# HBridge328.net
KiCad netlist of a schematic drawn in EAGLE
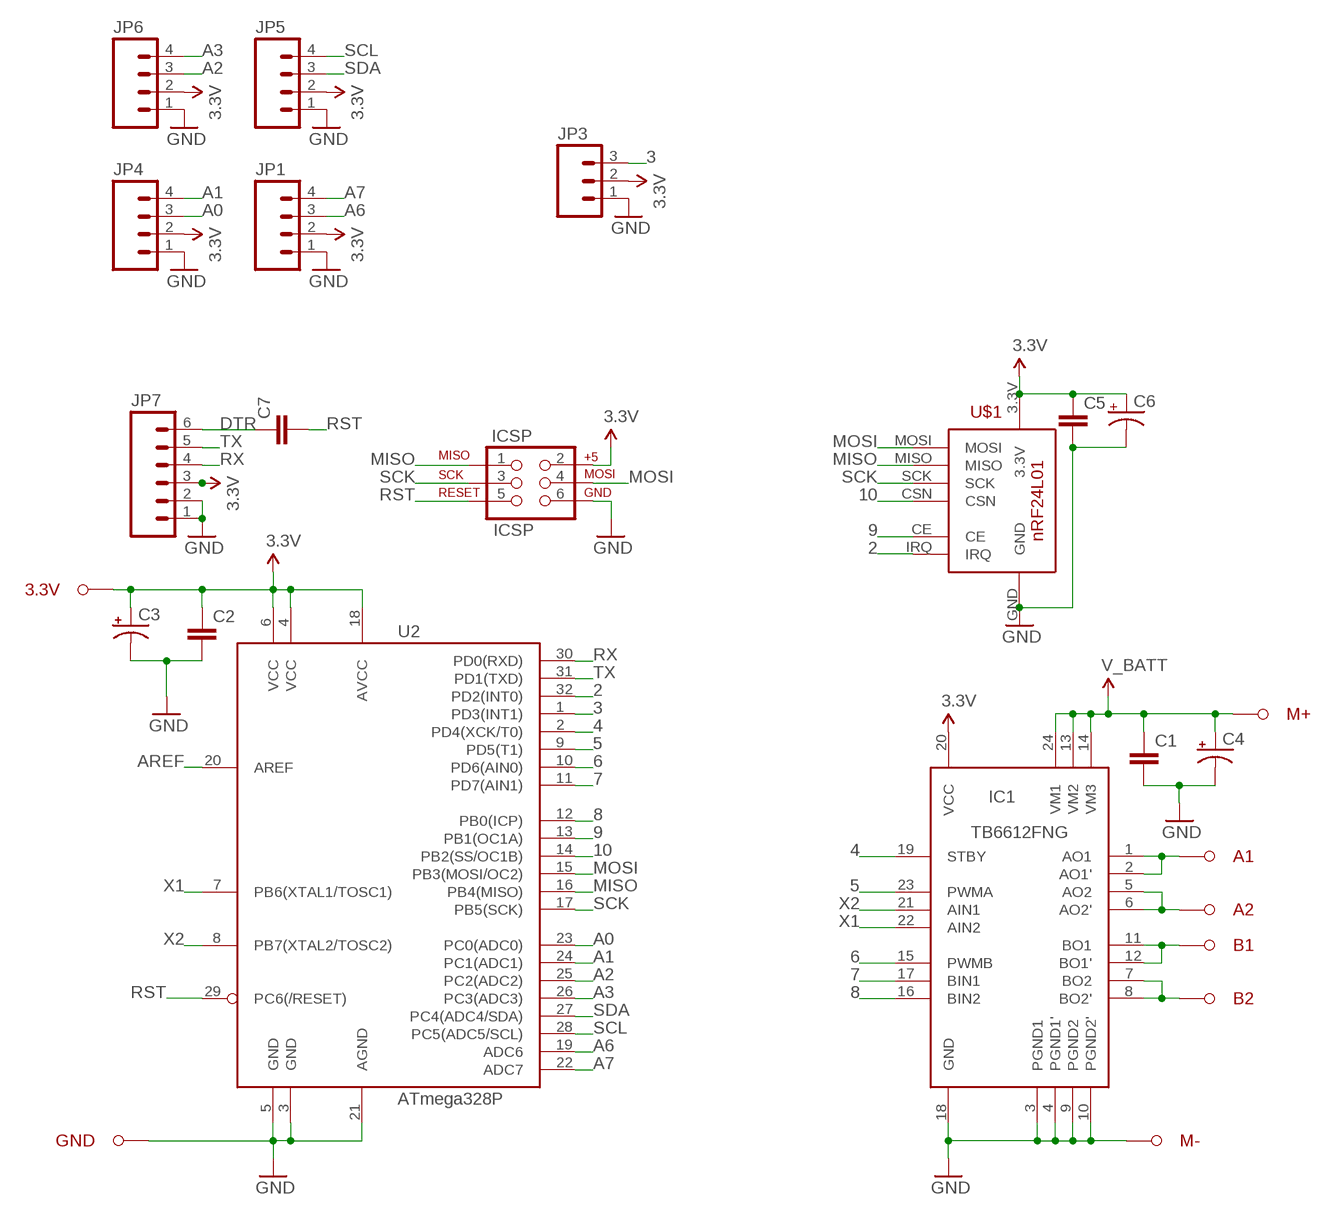
[diagram p0: schematic, sheet 1]

(export (version "E")
  (design (tool "Eeschema 10.0.6"))
  (components
    (comp (ref "3.3V")
      (value "M1")
      (footprint "eagle-import:M1_NO_STRAIN")
      (libsource (lib "eagle-import") (part "M1"))
    )
    (comp (ref "A1")
      (value "M1")
      (footprint "eagle-import:M1_NO_STRAIN")
      (libsource (lib "eagle-import") (part "M1"))
    )
    (comp (ref "A2")
      (value "M1")
      (footprint "eagle-import:M1_NO_STRAIN")
      (libsource (lib "eagle-import") (part "M1"))
    )
    (comp (ref "B1")
      (value "M1")
      (footprint "eagle-import:M1_NO_STRAIN")
      (libsource (lib "eagle-import") (part "M1"))
    )
    (comp (ref "B2")
      (value "M1")
      (footprint "eagle-import:M1_NO_STRAIN")
      (libsource (lib "eagle-import") (part "M1"))
    )
    (comp (ref "C1")
      (value "CAP1206")
      (footprint "eagle-import:1206")
      (libsource (lib "eagle-import") (part "CAP1206"))
    )
    (comp (ref "C2")
      (value "CAP1206")
      (footprint "eagle-import:1206")
      (libsource (lib "eagle-import") (part "CAP1206"))
    )
    (comp (ref "C3")
      (value "CAP_POL1206")
      (footprint "eagle-import:EIA3216")
      (libsource (lib "eagle-import") (part "CAP_POL1206"))
    )
    (comp (ref "C4")
      (value "CAP_POL1206")
      (footprint "eagle-import:EIA3216")
      (libsource (lib "eagle-import") (part "CAP_POL1206"))
    )
    (comp (ref "C5")
      (value "CAP1206")
      (footprint "eagle-import:1206")
      (libsource (lib "eagle-import") (part "CAP1206"))
    )
    (comp (ref "C6")
      (value "CAP_POL1206")
      (footprint "eagle-import:EIA3216")
      (libsource (lib "eagle-import") (part "CAP_POL1206"))
    )
    (comp (ref "C7")
      (value "CAP1206")
      (footprint "eagle-import:1206")
      (libsource (lib "eagle-import") (part "CAP1206"))
    )
    (comp (ref "GND")
      (value "M1")
      (footprint "eagle-import:M1_NO_STRAIN")
      (libsource (lib "eagle-import") (part "M1"))
    )
    (comp (ref "IC1")
      (value "TB6612")
      (footprint "eagle-import:SSOP24")
      (libsource (lib "eagle-import") (part "TB6612FNG"))
    )
    (comp (ref "ICSP")
      (value "ICSP")
      (footprint "eagle-import:2X3-NS")
      (libsource (lib "eagle-import") (part "AVR_SPI_PRG_6LABELED"))
    )
    (comp (ref "JP1")
      (value "M04PTH")
      (footprint "eagle-import:1X04")
      (libsource (lib "eagle-import") (part "M04PTH"))
    )
    (comp (ref "JP3")
      (value "M03PTH")
      (footprint "eagle-import:1X03")
      (libsource (lib "eagle-import") (part "M03PTH"))
    )
    (comp (ref "JP4")
      (value "M04PTH")
      (footprint "eagle-import:1X04")
      (libsource (lib "eagle-import") (part "M04PTH"))
    )
    (comp (ref "JP5")
      (value "M04PTH")
      (footprint "eagle-import:1X04")
      (libsource (lib "eagle-import") (part "M04PTH"))
    )
    (comp (ref "JP6")
      (value "M04PTH")
      (footprint "eagle-import:1X04")
      (libsource (lib "eagle-import") (part "M04PTH"))
    )
    (comp (ref "JP7")
      (value "M06SILK_FEMALE_PTH")
      (footprint "eagle-import:1X06")
      (libsource (lib "eagle-import") (part "M06SILK_FEMALE_PTH"))
    )
    (comp (ref "M+")
      (value "M1")
      (footprint "eagle-import:M1_NO_STRAIN")
      (libsource (lib "eagle-import") (part "M1"))
    )
    (comp (ref "M-")
      (value "M1")
      (footprint "eagle-import:M1_NO_STRAIN")
      (libsource (lib "eagle-import") (part "M1"))
    )
    (comp (ref "U$1")
      (value "RF24_MODULE")
      (footprint "eagle-import:RF24_SOCKET")
      (libsource (lib "eagle-import") (part "RF24_MODULE"))
    )
    (comp (ref "U2")
      (value "ATmega328P")
      (footprint "eagle-import:TQFP32-08")
      (libsource (lib "eagle-import") (part "ATMEGA328P_TQFP"))
    )
  )
  (nets
    (net (code "1") (name "/2") (class "Default")
      (node (ref "U$1") (pin "IRQ") (pinfunction "IRQ_IRQ") (pintype "bidirectional"))
      (node (ref "U2") (pin "32") (pinfunction "PD2(INT0)_32") (pintype "bidirectional"))
    )
    (net (code "2") (name "/3") (class "Default")
      (node (ref "JP3") (pin "3") (pinfunction "3_3") (pintype "passive"))
      (node (ref "U2") (pin "1") (pinfunction "PD3(INT1)_1") (pintype "bidirectional"))
    )
    (net (code "3") (name "/4") (class "Default")
      (node (ref "IC1") (pin "19") (pinfunction "STBY_19") (pintype "input"))
      (node (ref "U2") (pin "2") (pinfunction "PD4(XCK/T0)_2") (pintype "bidirectional"))
    )
    (net (code "4") (name "/5") (class "Default")
      (node (ref "IC1") (pin "23") (pinfunction "PWMA_23") (pintype "input"))
      (node (ref "U2") (pin "9") (pinfunction "PD5(T1)_9") (pintype "bidirectional"))
    )
    (net (code "5") (name "/6") (class "Default")
      (node (ref "IC1") (pin "15") (pinfunction "PWMB_15") (pintype "input"))
      (node (ref "U2") (pin "10") (pinfunction "PD6(AIN0)_10") (pintype "bidirectional"))
    )
    (net (code "6") (name "/7") (class "Default")
      (node (ref "IC1") (pin "17") (pinfunction "BIN1_17") (pintype "input"))
      (node (ref "U2") (pin "11") (pinfunction "PD7(AIN1)_11") (pintype "bidirectional"))
    )
    (net (code "7") (name "/8") (class "Default")
      (node (ref "IC1") (pin "16") (pinfunction "BIN2_16") (pintype "input"))
      (node (ref "U2") (pin "12") (pinfunction "PB0(ICP)_12") (pintype "bidirectional"))
    )
    (net (code "8") (name "/9") (class "Default")
      (node (ref "U$1") (pin "CE") (pinfunction "CE_CE") (pintype "bidirectional"))
      (node (ref "U2") (pin "13") (pinfunction "PB1(OC1A)_13") (pintype "bidirectional"))
    )
    (net (code "9") (name "/10") (class "Default")
      (node (ref "U$1") (pin "CSN") (pinfunction "CSN_CSN") (pintype "bidirectional"))
      (node (ref "U2") (pin "14") (pinfunction "PB2(SS/OC1B)_14") (pintype "bidirectional"))
    )
    (net (code "10") (name "/A0") (class "Default")
      (node (ref "JP4") (pin "3") (pinfunction "3_3") (pintype "passive"))
      (node (ref "U2") (pin "23") (pinfunction "PC0(ADC0)_23") (pintype "bidirectional"))
    )
    (net (code "11") (name "/A1") (class "Default")
      (node (ref "JP4") (pin "4") (pinfunction "4_4") (pintype "passive"))
      (node (ref "U2") (pin "24") (pinfunction "PC1(ADC1)_24") (pintype "bidirectional"))
    )
    (net (code "12") (name "/A2") (class "Default")
      (node (ref "JP6") (pin "3") (pinfunction "3_3") (pintype "passive"))
      (node (ref "U2") (pin "25") (pinfunction "PC2(ADC2)_25") (pintype "bidirectional"))
    )
    (net (code "13") (name "/A3") (class "Default")
      (node (ref "JP6") (pin "4") (pinfunction "4_4") (pintype "passive"))
      (node (ref "U2") (pin "26") (pinfunction "PC3(ADC3)_26") (pintype "bidirectional"))
    )
    (net (code "14") (name "/A6") (class "Default")
      (node (ref "JP1") (pin "3") (pinfunction "3_3") (pintype "passive"))
      (node (ref "U2") (pin "19") (pinfunction "ADC6_19") (pintype "bidirectional"))
    )
    (net (code "15") (name "/A7") (class "Default")
      (node (ref "JP1") (pin "4") (pinfunction "4_4") (pintype "passive"))
      (node (ref "U2") (pin "22") (pinfunction "ADC7_22") (pintype "bidirectional"))
    )
    (net (code "16") (name "/AREF") (class "Default")
      (node (ref "U2") (pin "20") (pinfunction "AREF_20") (pintype "bidirectional"))
    )
    (net (code "17") (name "/DTR") (class "Default")
      (node (ref "C7") (pin "1") (pinfunction "1_1") (pintype "passive"))
      (node (ref "JP7") (pin "6") (pinfunction "6_6") (pintype "passive"))
    )
    (net (code "18") (name "/MISO") (class "Default")
      (node (ref "ICSP") (pin "1") (pinfunction "MISO_1") (pintype "passive"))
      (node (ref "U$1") (pin "MISO") (pinfunction "MISO_MISO") (pintype "bidirectional"))
      (node (ref "U2") (pin "16") (pinfunction "PB4(MISO)_16") (pintype "bidirectional"))
    )
    (net (code "19") (name "/MOSI") (class "Default")
      (node (ref "ICSP") (pin "4") (pinfunction "MOSI_4") (pintype "passive"))
      (node (ref "U$1") (pin "MOSI") (pinfunction "MOSI_MOSI") (pintype "bidirectional"))
      (node (ref "U2") (pin "15") (pinfunction "PB3(MOSI/OC2)_15") (pintype "bidirectional"))
    )
    (net (code "20") (name "/RST") (class "Default")
      (node (ref "C7") (pin "2") (pinfunction "2_2") (pintype "passive"))
      (node (ref "ICSP") (pin "5") (pinfunction "RST_5") (pintype "passive"))
      (node (ref "U2") (pin "29") (pinfunction "PC6(/RESET)_29") (pintype "bidirectional"))
    )
    (net (code "21") (name "/RX") (class "Default")
      (node (ref "JP7") (pin "4") (pinfunction "4_4") (pintype "passive"))
      (node (ref "U2") (pin "30") (pinfunction "PD0(RXD)_30") (pintype "bidirectional"))
    )
    (net (code "22") (name "/SCK") (class "Default")
      (node (ref "ICSP") (pin "3") (pinfunction "SCK_3") (pintype "passive"))
      (node (ref "U$1") (pin "SCK") (pinfunction "SCK_SCK") (pintype "bidirectional"))
      (node (ref "U2") (pin "17") (pinfunction "PB5(SCK)_17") (pintype "bidirectional"))
    )
    (net (code "23") (name "/SCL") (class "Default")
      (node (ref "JP5") (pin "4") (pinfunction "4_4") (pintype "passive"))
      (node (ref "U2") (pin "28") (pinfunction "PC5(ADC5/SCL)_28") (pintype "bidirectional"))
    )
    (net (code "24") (name "/SDA") (class "Default")
      (node (ref "JP5") (pin "3") (pinfunction "3_3") (pintype "passive"))
      (node (ref "U2") (pin "27") (pinfunction "PC4(ADC4/SDA)_27") (pintype "bidirectional"))
    )
    (net (code "25") (name "/TX") (class "Default")
      (node (ref "JP7") (pin "5") (pinfunction "5_5") (pintype "passive"))
      (node (ref "U2") (pin "31") (pinfunction "PD1(TXD)_31") (pintype "bidirectional"))
    )
    (net (code "26") (name "/X1") (class "Default")
      (node (ref "IC1") (pin "22") (pinfunction "AIN2_22") (pintype "input"))
      (node (ref "U2") (pin "7") (pinfunction "PB6(XTAL1/TOSC1)_7") (pintype "bidirectional"))
    )
    (net (code "27") (name "/X2") (class "Default")
      (node (ref "IC1") (pin "21") (pinfunction "AIN1_21") (pintype "input"))
      (node (ref "U2") (pin "8") (pinfunction "PB7(XTAL2/TOSC2)_8") (pintype "bidirectional"))
    )
    (net (code "28") (name "3.3V") (class "Default")
      (node (ref "3.3V") (pin "P$1") (pinfunction "P$1_P$1") (pintype "bidirectional"))
      (node (ref "C2") (pin "1") (pinfunction "1_1") (pintype "passive"))
      (node (ref "C3") (pin "A") (pinfunction "+_A") (pintype "passive"))
      (node (ref "C5") (pin "1") (pinfunction "1_1") (pintype "passive"))
      (node (ref "C6") (pin "A") (pinfunction "+_A") (pintype "passive"))
      (node (ref "IC1") (pin "20") (pinfunction "VCC_20") (pintype "power_in"))
      (node (ref "ICSP") (pin "2") (pinfunction "V+_2") (pintype "passive"))
      (node (ref "JP1") (pin "2") (pinfunction "2_2") (pintype "passive"))
      (node (ref "JP3") (pin "2") (pinfunction "2_2") (pintype "passive"))
      (node (ref "JP4") (pin "2") (pinfunction "2_2") (pintype "passive"))
      (node (ref "JP5") (pin "2") (pinfunction "2_2") (pintype "passive"))
      (node (ref "JP6") (pin "2") (pinfunction "2_2") (pintype "passive"))
      (node (ref "JP7") (pin "3") (pinfunction "3_3") (pintype "passive"))
      (node (ref "U$1") (pin "3.3V") (pinfunction "3.3V_3.3V") (pintype "bidirectional"))
      (node (ref "U2") (pin "18") (pinfunction "AVCC_18") (pintype "bidirectional"))
      (node (ref "U2") (pin "4") (pinfunction "VCC_4") (pintype "bidirectional"))
      (node (ref "U2") (pin "6") (pinfunction "VCC_6") (pintype "bidirectional"))
    )
    (net (code "29") (name "GND") (class "Default")
      (node (ref "C1") (pin "2") (pinfunction "2_2") (pintype "passive"))
      (node (ref "C2") (pin "2") (pinfunction "2_2") (pintype "passive"))
      (node (ref "C3") (pin "C") (pinfunction "-_C") (pintype "passive"))
      (node (ref "C4") (pin "C") (pinfunction "-_C") (pintype "passive"))
      (node (ref "C5") (pin "2") (pinfunction "2_2") (pintype "passive"))
      (node (ref "C6") (pin "C") (pinfunction "-_C") (pintype "passive"))
      (node (ref "GND") (pin "P$1") (pinfunction "P$1_P$1") (pintype "bidirectional"))
      (node (ref "IC1") (pin "10") (pinfunction "PGND2'_10") (pintype "power_in"))
      (node (ref "IC1") (pin "18") (pinfunction "GND_18") (pintype "power_in"))
      (node (ref "IC1") (pin "3") (pinfunction "PGND1_3") (pintype "power_in"))
      (node (ref "IC1") (pin "4") (pinfunction "PGND1'_4") (pintype "power_in"))
      (node (ref "IC1") (pin "9") (pinfunction "PGND2_9") (pintype "power_in"))
      (node (ref "ICSP") (pin "6") (pinfunction "GND_6") (pintype "passive"))
      (node (ref "JP1") (pin "1") (pinfunction "1_1") (pintype "passive"))
      (node (ref "JP3") (pin "1") (pinfunction "1_1") (pintype "passive"))
      (node (ref "JP4") (pin "1") (pinfunction "1_1") (pintype "passive"))
      (node (ref "JP5") (pin "1") (pinfunction "1_1") (pintype "passive"))
      (node (ref "JP6") (pin "1") (pinfunction "1_1") (pintype "passive"))
      (node (ref "JP7") (pin "1") (pinfunction "1_1") (pintype "passive"))
      (node (ref "JP7") (pin "2") (pinfunction "2_2") (pintype "passive"))
      (node (ref "M-") (pin "P$1") (pinfunction "P$1_P$1") (pintype "bidirectional"))
      (node (ref "U$1") (pin "GND") (pinfunction "GND_GND") (pintype "bidirectional"))
      (node (ref "U2") (pin "21") (pinfunction "AGND_21") (pintype "bidirectional"))
      (node (ref "U2") (pin "3") (pinfunction "GND_3") (pintype "bidirectional"))
      (node (ref "U2") (pin "5") (pinfunction "GND_5") (pintype "bidirectional"))
    )
    (net (code "30") (name "Net-(IC1-AO1')") (class "Default")
      (node (ref "A1") (pin "P$1") (pinfunction "P$1_P$1") (pintype "bidirectional"))
      (node (ref "IC1") (pin "1") (pinfunction "AO1_1") (pintype "output"))
      (node (ref "IC1") (pin "2") (pinfunction "AO1'_2") (pintype "output"))
    )
    (net (code "31") (name "Net-(IC1-AO2')") (class "Default")
      (node (ref "A2") (pin "P$1") (pinfunction "P$1_P$1") (pintype "bidirectional"))
      (node (ref "IC1") (pin "5") (pinfunction "AO2_5") (pintype "output"))
      (node (ref "IC1") (pin "6") (pinfunction "AO2'_6") (pintype "output"))
    )
    (net (code "32") (name "Net-(IC1-BO1')") (class "Default")
      (node (ref "B1") (pin "P$1") (pinfunction "P$1_P$1") (pintype "bidirectional"))
      (node (ref "IC1") (pin "11") (pinfunction "BO1_11") (pintype "output"))
      (node (ref "IC1") (pin "12") (pinfunction "BO1'_12") (pintype "output"))
    )
    (net (code "33") (name "Net-(IC1-BO2')") (class "Default")
      (node (ref "B2") (pin "P$1") (pinfunction "P$1_P$1") (pintype "bidirectional"))
      (node (ref "IC1") (pin "7") (pinfunction "BO2_7") (pintype "output"))
      (node (ref "IC1") (pin "8") (pinfunction "BO2'_8") (pintype "output"))
    )
    (net (code "34") (name "V_BATT") (class "Default")
      (node (ref "C1") (pin "1") (pinfunction "1_1") (pintype "passive"))
      (node (ref "C4") (pin "A") (pinfunction "+_A") (pintype "passive"))
      (node (ref "IC1") (pin "13") (pinfunction "VM2_13") (pintype "power_in"))
      (node (ref "IC1") (pin "14") (pinfunction "VM3_14") (pintype "power_in"))
      (node (ref "IC1") (pin "24") (pinfunction "VM1_24") (pintype "power_in"))
      (node (ref "M+") (pin "P$1") (pinfunction "P$1_P$1") (pintype "bidirectional"))
    )
  )
)
